# BHOnOfreESP01.net
KiCad netlist of a schematic drawn in EAGLE
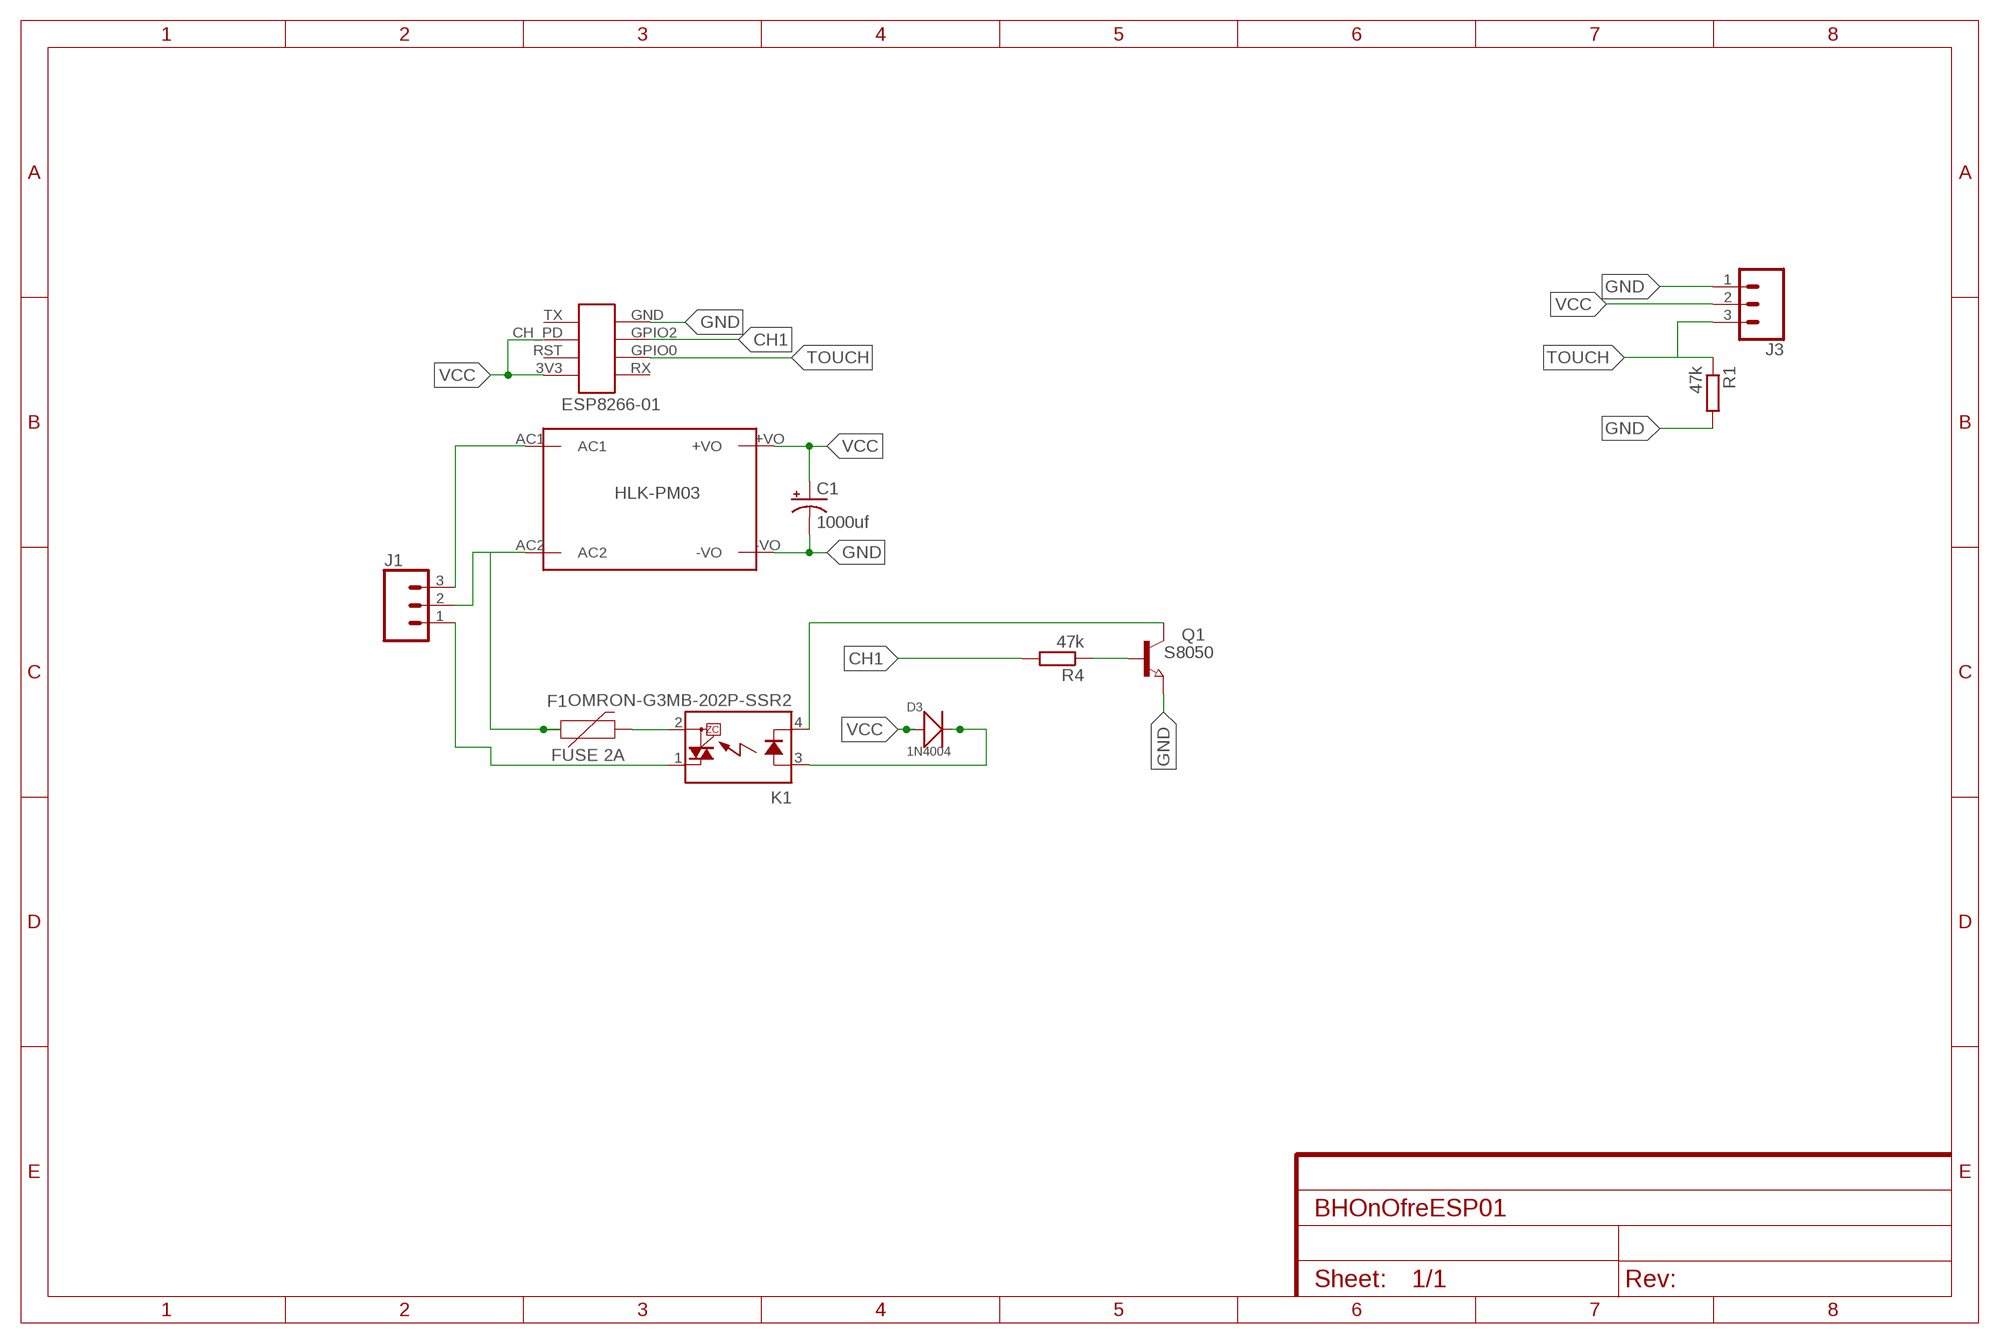
[diagram p0: schematic, sheet 1]

(export (version "E")
  (design (tool "Eeschema 10.0.6"))
  (components
    (comp (ref "C1")
      (value "1000uf")
      (footprint "eagle-import:140CLH-1010")
      (libsource (lib "eagle-import") (part "CPOL-US140CLH-1010"))
    )
    (comp (ref "D3")
      (value "1N4004")
      (footprint "eagle-import:DO-214AC")
      (fields (field (name "MPN") "1N4007"))
      (libsource (lib "eagle-import") (part "DIODE-GEN-PURPOSE-1KV-1A(DO-214AC)"))
    )
    (comp (ref "F1")
      (value "FUSE 2A")
      (footprint "eagle-import:PTH")
      (libsource (lib "eagle-import") (part "PPTC_PTH"))
    )
    (comp (ref "J1")
      (value "CONN_03-SCREW-5MM")
      (footprint "eagle-import:SCREWTERMINAL-5MM-3")
      (libsource (lib "eagle-import") (part "CONN_03-SCREW-5MM"))
    )
    (comp (ref "J3")
      (value "CONN_03")
      (footprint "eagle-import:1X03")
      (libsource (lib "eagle-import") (part "CONN_03"))
    )
    (comp (ref "K1")
      (value "OMRON-G3MB-202P-SSR2")
      (footprint "eagle-import:OMRON-G3MB-202P-SSR")
      (fields (field (name "MPN") "S202S02F"))
      (libsource (lib "eagle-import") (part "OMRON-G3MB-202P-SSR2"))
    )
    (comp (ref "Q1")
      (value "S8050")
      (footprint "eagle-import:SOT23")
      (libsource (lib "eagle-import") (part "NPN-TRANSISTOR_SOT23"))
    )
    (comp (ref "R1")
      (value "47k")
      (footprint "eagle-import:R0603")
      (libsource (lib "eagle-import") (part "R-EU_R0603"))
    )
    (comp (ref "R4")
      (value "47k")
      (footprint "eagle-import:R0603")
      (libsource (lib "eagle-import") (part "R-EU_R0603"))
    )
    (comp (ref "U$2")
      (value "HLK-PM03")
      (footprint "eagle-import:HLK-PM03")
      (libsource (lib "eagle-import") (part "HLK-PM03"))
    )
    (comp (ref "U$3")
      (value "ESP8266-01")
      (footprint "eagle-import:ESP8266-01")
      (libsource (lib "eagle-import") (part "ESP8266-01"))
    )
  )
  (nets
    (net (code "1") (name "CH1") (class "Default")
      (node (ref "R4") (pin "2") (pinfunction "2_2") (pintype "passive"))
      (node (ref "U$3") (pin "GPIO2") (pinfunction "GPIO2_GPIO2") (pintype "bidirectional"))
    )
    (net (code "2") (name "GND") (class "Default")
      (node (ref "C1") (pin "-") (pinfunction "-_-") (pintype "passive"))
      (node (ref "J3") (pin "1") (pinfunction "1_1") (pintype "passive"))
      (node (ref "Q1") (pin "2") (pinfunction "E_2") (pintype "passive"))
      (node (ref "R1") (pin "2") (pinfunction "2_2") (pintype "passive"))
      (node (ref "U$2") (pin "-VO") (pinfunction "-VO_-VO") (pintype "bidirectional"))
      (node (ref "U$3") (pin "GND") (pinfunction "GND_GND") (pintype "bidirectional"))
    )
    (net (code "3") (name "Net-(D3--)") (class "Default")
      (node (ref "D3") (pin "2") (pinfunction "-_2") (pintype "passive"))
      (node (ref "K1") (pin "3") (pinfunction "A_3") (pintype "passive"))
    )
    (net (code "4") (name "Net-(F1-1)") (class "Default")
      (node (ref "F1") (pin "P$1") (pinfunction "1_P$1") (pintype "bidirectional"))
      (node (ref "J1") (pin "2") (pinfunction "2_2") (pintype "passive"))
      (node (ref "U$2") (pin "AC2") (pinfunction "AC2_AC2") (pintype "bidirectional"))
    )
    (net (code "5") (name "Net-(F1-2)") (class "Default")
      (node (ref "F1") (pin "P$2") (pinfunction "2_P$2") (pintype "bidirectional"))
      (node (ref "K1") (pin "2") (pinfunction "DS2_2") (pintype "passive"))
    )
    (net (code "6") (name "Net-(J1-Pad3)") (class "Default")
      (node (ref "J1") (pin "3") (pinfunction "3_3") (pintype "passive"))
      (node (ref "U$2") (pin "AC1") (pinfunction "AC1_AC1") (pintype "bidirectional"))
    )
    (net (code "7") (name "Net-(K1-DS1)") (class "Default")
      (node (ref "J1") (pin "1") (pinfunction "1_1") (pintype "passive"))
      (node (ref "K1") (pin "1") (pinfunction "DS1_1") (pintype "passive"))
    )
    (net (code "8") (name "Net-(K1-K)") (class "Default")
      (node (ref "K1") (pin "4") (pinfunction "K_4") (pintype "passive"))
      (node (ref "Q1") (pin "3") (pinfunction "C_3") (pintype "passive"))
    )
    (net (code "9") (name "Net-(Q1-B)") (class "Default")
      (node (ref "Q1") (pin "1") (pinfunction "B_1") (pintype "passive"))
      (node (ref "R4") (pin "1") (pinfunction "1_1") (pintype "passive"))
    )
    (net (code "10") (name "TOUCH") (class "Default")
      (node (ref "J3") (pin "3") (pinfunction "3_3") (pintype "passive"))
      (node (ref "R1") (pin "1") (pinfunction "1_1") (pintype "passive"))
      (node (ref "U$3") (pin "GPIO0") (pinfunction "GPIO0_GPIO0") (pintype "bidirectional"))
    )
    (net (code "11") (name "VCC") (class "Default")
      (node (ref "C1") (pin "+") (pinfunction "+_+") (pintype "passive"))
      (node (ref "D3") (pin "1") (pinfunction "+_1") (pintype "passive"))
      (node (ref "J3") (pin "2") (pinfunction "2_2") (pintype "passive"))
      (node (ref "U$2") (pin "+VO") (pinfunction "+VO_+VO") (pintype "bidirectional"))
      (node (ref "U$3") (pin "3V3") (pinfunction "3V3_3V3") (pintype "bidirectional"))
      (node (ref "U$3") (pin "CH_PD") (pinfunction "CH_PD_CH_PD") (pintype "bidirectional"))
    )
    (net (code "12") (name "unconnected-(U$3-PadRST)") (class "Default")
      (node (ref "U$3") (pin "RST") (pinfunction "RST_RST") (pintype "bidirectional"))
    )
    (net (code "13") (name "unconnected-(U$3-PadRX)") (class "Default")
      (node (ref "U$3") (pin "RX") (pinfunction "RX_RX") (pintype "bidirectional"))
    )
    (net (code "14") (name "unconnected-(U$3-PadTX)") (class "Default")
      (node (ref "U$3") (pin "TX") (pinfunction "TX_TX") (pintype "bidirectional"))
    )
  )
)
